# Power_Supply.net
KiCad netlist of a schematic drawn in Altium Designer
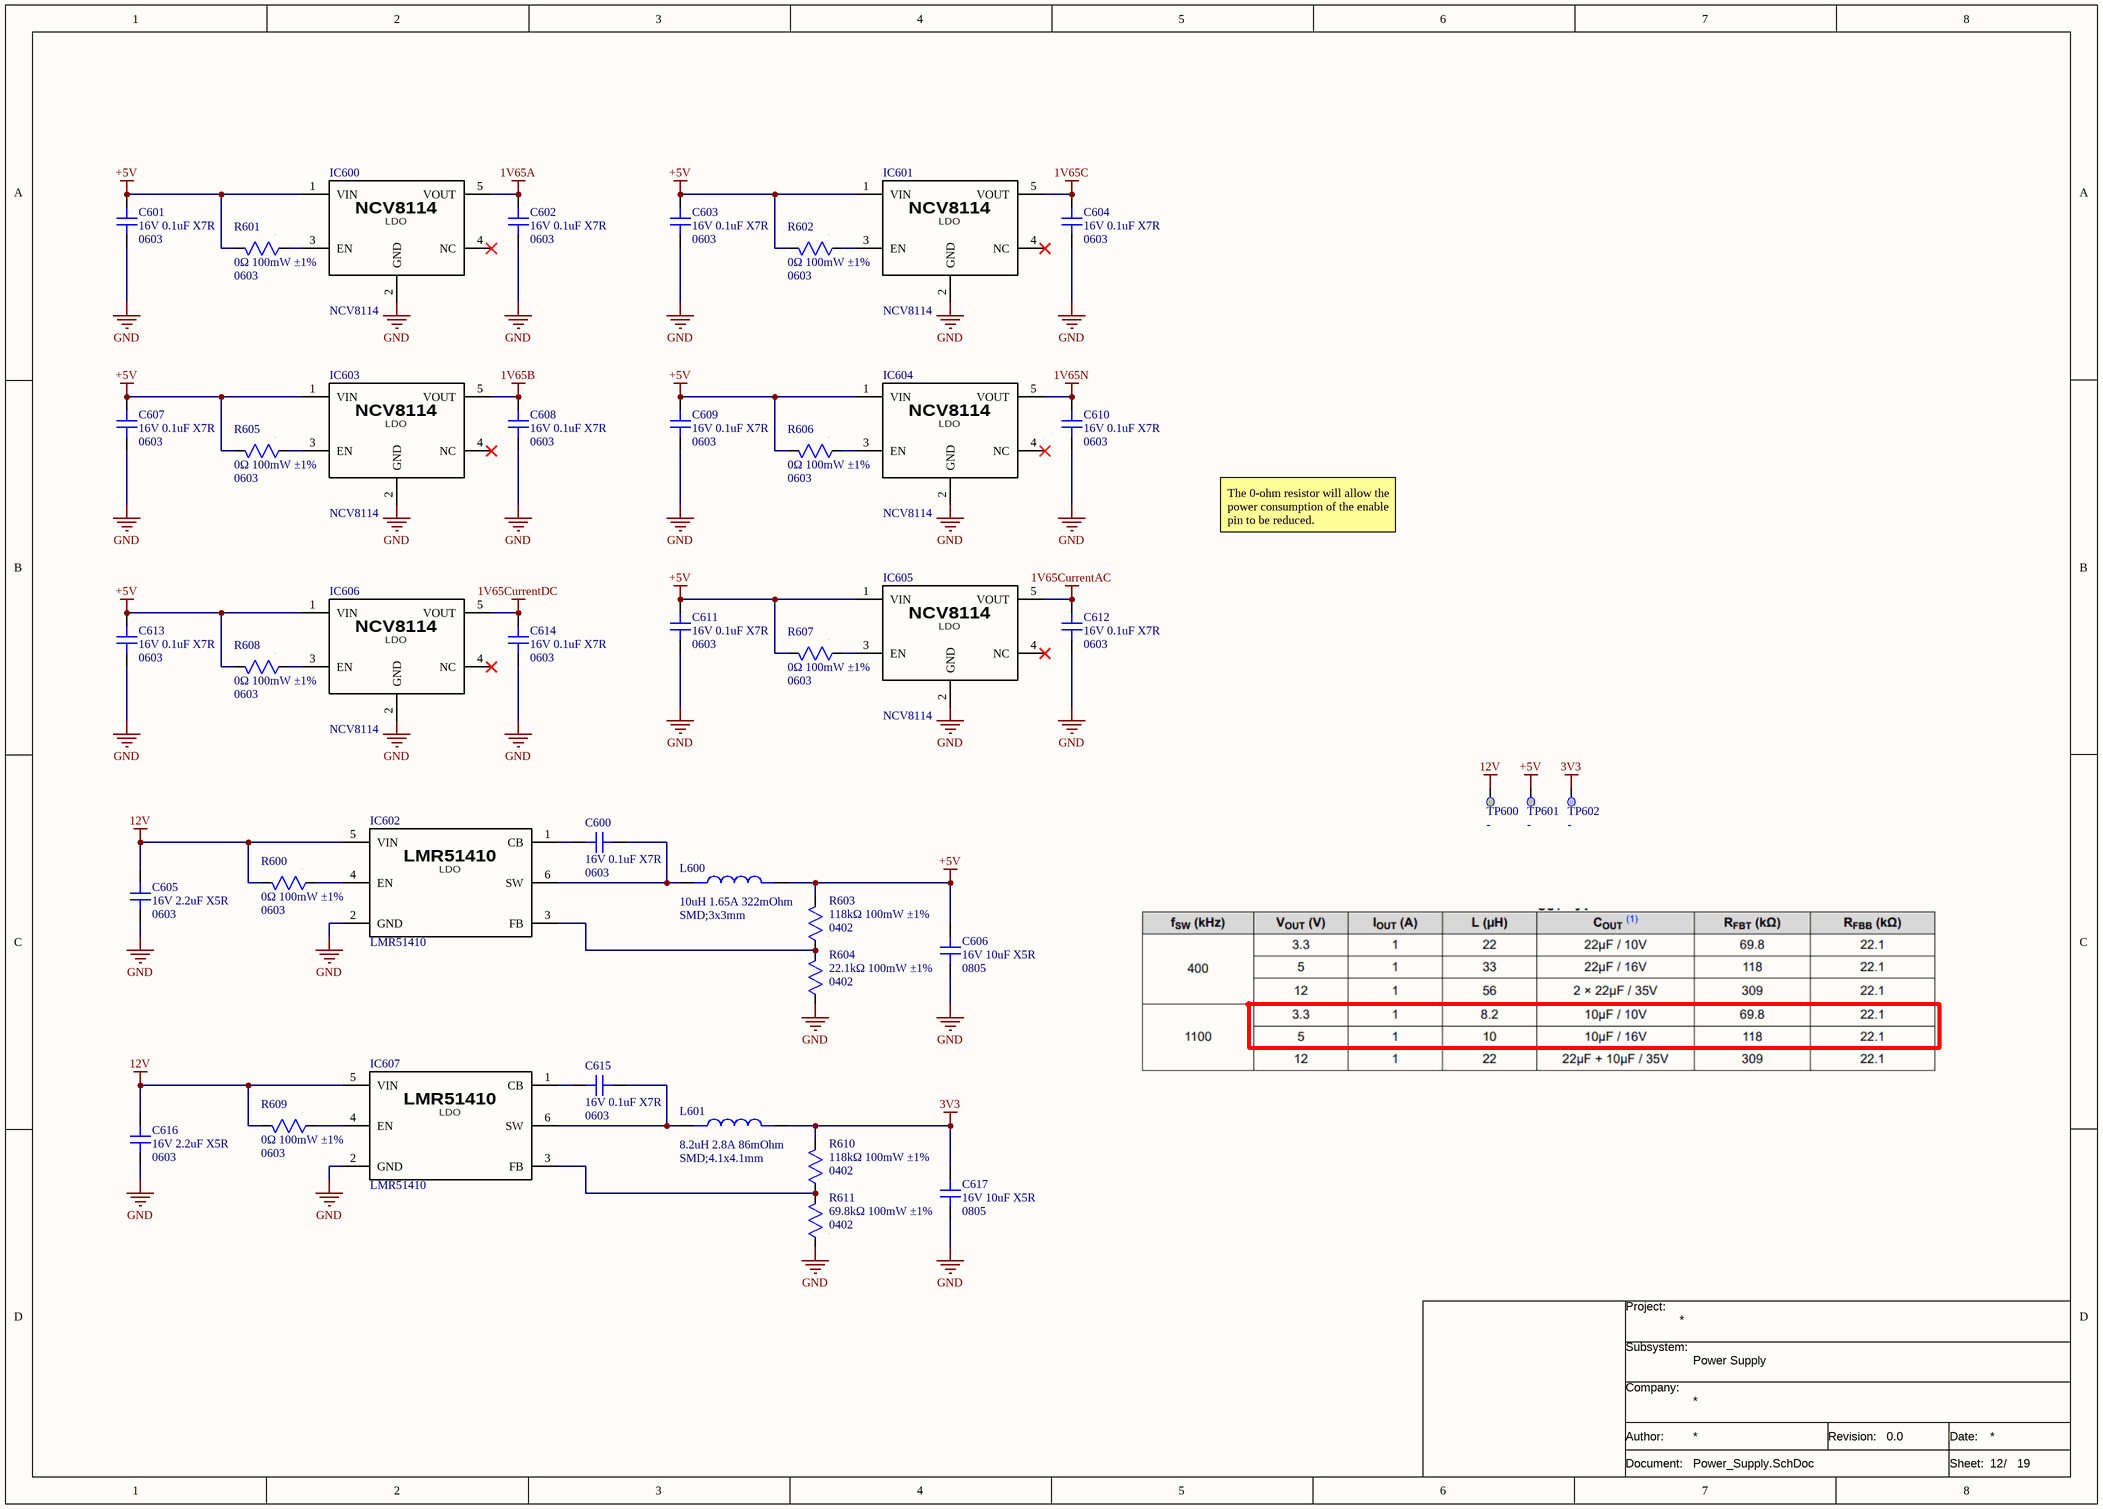
[diagram p0: Power_Supply.SchDoc]

(export (version "E")
  (design (tool "Eeschema 10.0.6"))
  (components
    (comp (ref "C600")
      (value "16V 0.1uF X7R")
      (footprint "CAP SMD 0603")
      (description "Condensadores de cerámica multicapa (MLCC- SMD/SMT) WCAP-CSGP 0.1uF 0603 10% 16V MLCC")
      (fields
        (field (name "PACKAGE") "0603")
        (field (name "MPN") "885012206046")
        (field (name "MANUFACTURER") "Wurth Elektronik")
      )
      (libsource (lib "eUSR_Database") (part "CAP non polarized"))
    )
    (comp (ref "C601")
      (value "16V 0.1uF X7R")
      (footprint "CAP SMD 0603")
      (description "Condensadores de cerámica multicapa (MLCC- SMD/SMT) WCAP-CSGP 0.1uF 0603 10% 16V MLCC")
      (fields
        (field (name "PACKAGE") "0603")
        (field (name "MPN") "885012206046")
        (field (name "MANUFACTURER") "Wurth Elektronik")
      )
      (libsource (lib "eUSR_Database") (part "CAP non polarized"))
    )
    (comp (ref "C602")
      (value "16V 0.1uF X7R")
      (footprint "CAP SMD 0603")
      (description "Condensadores de cerámica multicapa (MLCC- SMD/SMT) WCAP-CSGP 0.1uF 0603 10% 16V MLCC")
      (fields
        (field (name "PACKAGE") "0603")
        (field (name "MPN") "885012206046")
        (field (name "MANUFACTURER") "Wurth Elektronik")
      )
      (libsource (lib "eUSR_Database") (part "CAP non polarized"))
    )
    (comp (ref "C603")
      (value "16V 0.1uF X7R")
      (footprint "CAP SMD 0603")
      (description "Condensadores de cerámica multicapa (MLCC- SMD/SMT) WCAP-CSGP 0.1uF 0603 10% 16V MLCC")
      (fields
        (field (name "PACKAGE") "0603")
        (field (name "MPN") "885012206046")
        (field (name "MANUFACTURER") "Wurth Elektronik")
      )
      (libsource (lib "eUSR_Database") (part "CAP non polarized"))
    )
    (comp (ref "C604")
      (value "16V 0.1uF X7R")
      (footprint "CAP SMD 0603")
      (description "Condensadores de cerámica multicapa (MLCC- SMD/SMT) WCAP-CSGP 0.1uF 0603 10% 16V MLCC")
      (fields
        (field (name "PACKAGE") "0603")
        (field (name "MPN") "885012206046")
        (field (name "MANUFACTURER") "Wurth Elektronik")
      )
      (libsource (lib "eUSR_Database") (part "CAP non polarized"))
    )
    (comp (ref "C605")
      (value "16V 2.2uF X5R")
      (footprint "CAP SMD 0603")
      (description "Condensadores de cerámica multicapa (MLCC- SMD/SMT) WCAP-CSGP 2.2uF 16V 10%")
      (fields
        (field (name "PACKAGE") "0603")
        (field (name "MPN") "885012106029")
        (field (name "MANUFACTURER") "Wurth Elektronik")
      )
      (libsource (lib "eUSR_Database") (part "CAP non polarized"))
    )
    (comp (ref "C606")
      (value "16V 10uF X5R")
      (footprint "CAP SMD 0805")
      (description "Condensadores de cerámica multicapa (MLCC- SMD/SMT) WCAP-CSGP 10uF 0805 20% 16V MLCC")
      (fields
        (field (name "PACKAGE") "0805")
        (field (name "MPN") "885012107014")
        (field (name "MANUFACTURER") "Wurth Elektronik")
      )
      (libsource (lib "eUSR_Database") (part "CAP non polarized"))
    )
    (comp (ref "C607")
      (value "16V 0.1uF X7R")
      (footprint "CAP SMD 0603")
      (description "Condensadores de cerámica multicapa (MLCC- SMD/SMT) WCAP-CSGP 0.1uF 0603 10% 16V MLCC")
      (fields
        (field (name "PACKAGE") "0603")
        (field (name "MPN") "885012206046")
        (field (name "MANUFACTURER") "Wurth Elektronik")
      )
      (libsource (lib "eUSR_Database") (part "CAP non polarized"))
    )
    (comp (ref "C608")
      (value "16V 0.1uF X7R")
      (footprint "CAP SMD 0603")
      (description "Condensadores de cerámica multicapa (MLCC- SMD/SMT) WCAP-CSGP 0.1uF 0603 10% 16V MLCC")
      (fields
        (field (name "PACKAGE") "0603")
        (field (name "MPN") "885012206046")
        (field (name "MANUFACTURER") "Wurth Elektronik")
      )
      (libsource (lib "eUSR_Database") (part "CAP non polarized"))
    )
    (comp (ref "C609")
      (value "16V 0.1uF X7R")
      (footprint "CAP SMD 0603")
      (description "Condensadores de cerámica multicapa (MLCC- SMD/SMT) WCAP-CSGP 0.1uF 0603 10% 16V MLCC")
      (fields
        (field (name "PACKAGE") "0603")
        (field (name "MPN") "885012206046")
        (field (name "MANUFACTURER") "Wurth Elektronik")
      )
      (libsource (lib "eUSR_Database") (part "CAP non polarized"))
    )
    (comp (ref "C610")
      (value "16V 0.1uF X7R")
      (footprint "CAP SMD 0603")
      (description "Condensadores de cerámica multicapa (MLCC- SMD/SMT) WCAP-CSGP 0.1uF 0603 10% 16V MLCC")
      (fields
        (field (name "PACKAGE") "0603")
        (field (name "MPN") "885012206046")
        (field (name "MANUFACTURER") "Wurth Elektronik")
      )
      (libsource (lib "eUSR_Database") (part "CAP non polarized"))
    )
    (comp (ref "C611")
      (value "16V 0.1uF X7R")
      (footprint "CAP SMD 0603")
      (description "Condensadores de cerámica multicapa (MLCC- SMD/SMT) WCAP-CSGP 0.1uF 0603 10% 16V MLCC")
      (fields
        (field (name "PACKAGE") "0603")
        (field (name "MPN") "885012206046")
        (field (name "MANUFACTURER") "Wurth Elektronik")
      )
      (libsource (lib "eUSR_Database") (part "CAP non polarized"))
    )
    (comp (ref "C612")
      (value "16V 0.1uF X7R")
      (footprint "CAP SMD 0603")
      (description "Condensadores de cerámica multicapa (MLCC- SMD/SMT) WCAP-CSGP 0.1uF 0603 10% 16V MLCC")
      (fields
        (field (name "PACKAGE") "0603")
        (field (name "MPN") "885012206046")
        (field (name "MANUFACTURER") "Wurth Elektronik")
      )
      (libsource (lib "eUSR_Database") (part "CAP non polarized"))
    )
    (comp (ref "C613")
      (value "16V 0.1uF X7R")
      (footprint "CAP SMD 0603")
      (description "Condensadores de cerámica multicapa (MLCC- SMD/SMT) WCAP-CSGP 0.1uF 0603 10% 16V MLCC")
      (fields
        (field (name "PACKAGE") "0603")
        (field (name "MPN") "885012206046")
        (field (name "MANUFACTURER") "Wurth Elektronik")
      )
      (libsource (lib "eUSR_Database") (part "CAP non polarized"))
    )
    (comp (ref "C614")
      (value "16V 0.1uF X7R")
      (footprint "CAP SMD 0603")
      (description "Condensadores de cerámica multicapa (MLCC- SMD/SMT) WCAP-CSGP 0.1uF 0603 10% 16V MLCC")
      (fields
        (field (name "PACKAGE") "0603")
        (field (name "MPN") "885012206046")
        (field (name "MANUFACTURER") "Wurth Elektronik")
      )
      (libsource (lib "eUSR_Database") (part "CAP non polarized"))
    )
    (comp (ref "C615")
      (value "16V 0.1uF X7R")
      (footprint "CAP SMD 0603")
      (description "Condensadores de cerámica multicapa (MLCC- SMD/SMT) WCAP-CSGP 0.1uF 0603 10% 16V MLCC")
      (fields
        (field (name "PACKAGE") "0603")
        (field (name "MPN") "885012206046")
        (field (name "MANUFACTURER") "Wurth Elektronik")
      )
      (libsource (lib "eUSR_Database") (part "CAP non polarized"))
    )
    (comp (ref "C616")
      (value "16V 2.2uF X5R")
      (footprint "CAP SMD 0603")
      (description "Condensadores de cerámica multicapa (MLCC- SMD/SMT) WCAP-CSGP 2.2uF 16V 10%")
      (fields
        (field (name "PACKAGE") "0603")
        (field (name "MPN") "885012106029")
        (field (name "MANUFACTURER") "Wurth Elektronik")
      )
      (libsource (lib "eUSR_Database") (part "CAP non polarized"))
    )
    (comp (ref "C617")
      (value "16V 10uF X5R")
      (footprint "CAP SMD 0805")
      (description "Condensadores de cerámica multicapa (MLCC- SMD/SMT) WCAP-CSGP 10uF 0805 20% 16V MLCC")
      (fields
        (field (name "PACKAGE") "0805")
        (field (name "MPN") "885012107014")
        (field (name "MANUFACTURER") "Wurth Elektronik")
      )
      (libsource (lib "eUSR_Database") (part "CAP non polarized"))
    )
    (comp (ref "IC600")
      (value "NCV8114")
      (footprint "SOT-23-5")
      (description "Reguladores de voltaje LDO 300 MA CMOS LDO, AD OPTIO")
      (fields (field (name "MPN") "NCV8114ASN165T1G") (field (name "MANUFACTURER") "onsemi"))
      (libsource (lib "eUSR_Database") (part "NCV8114"))
    )
    (comp (ref "IC601")
      (value "NCV8114")
      (footprint "SOT-23-5")
      (description "Reguladores de voltaje LDO 300 MA CMOS LDO, AD OPTIO")
      (fields (field (name "MPN") "NCV8114ASN165T1G") (field (name "MANUFACTURER") "onsemi"))
      (libsource (lib "eUSR_Database") (part "NCV8114"))
    )
    (comp (ref "IC602")
      (value "LMR51410")
      (footprint "SOT-23-6")
      (description "Reguladores de tensión de conmutación SIMPLE SWITCHER 4V t o 42V 1A synchronou")
      (fields (field (name "MPN") "LMR51410YFDBVR") (field (name "MANUFACTURER") "Texas Instruments"))
      (libsource (lib "eUSR_Database") (part "LMR51410"))
    )
    (comp (ref "IC603")
      (value "NCV8114")
      (footprint "SOT-23-5")
      (description "Reguladores de voltaje LDO 300 MA CMOS LDO, AD OPTIO")
      (fields (field (name "MPN") "NCV8114ASN165T1G") (field (name "MANUFACTURER") "onsemi"))
      (libsource (lib "eUSR_Database") (part "NCV8114"))
    )
    (comp (ref "IC604")
      (value "NCV8114")
      (footprint "SOT-23-5")
      (description "Reguladores de voltaje LDO 300 MA CMOS LDO, AD OPTIO")
      (fields (field (name "MPN") "NCV8114ASN165T1G") (field (name "MANUFACTURER") "onsemi"))
      (libsource (lib "eUSR_Database") (part "NCV8114"))
    )
    (comp (ref "IC605")
      (value "NCV8114")
      (footprint "SOT-23-5")
      (description "Reguladores de voltaje LDO 300 MA CMOS LDO, AD OPTIO")
      (fields (field (name "MPN") "NCV8114ASN165T1G") (field (name "MANUFACTURER") "onsemi"))
      (libsource (lib "eUSR_Database") (part "NCV8114"))
    )
    (comp (ref "IC606")
      (value "NCV8114")
      (footprint "SOT-23-5")
      (description "Reguladores de voltaje LDO 300 MA CMOS LDO, AD OPTIO")
      (fields (field (name "MPN") "NCV8114ASN165T1G") (field (name "MANUFACTURER") "onsemi"))
      (libsource (lib "eUSR_Database") (part "NCV8114"))
    )
    (comp (ref "IC607")
      (value "LMR51410")
      (footprint "SOT-23-6")
      (description "Reguladores de tensión de conmutación SIMPLE SWITCHER 4V t o 42V 1A synchronou")
      (fields (field (name "MPN") "LMR51410YFDBVR") (field (name "MANUFACTURER") "Texas Instruments"))
      (libsource (lib "eUSR_Database") (part "LMR51410"))
    )
    (comp (ref "L600")
      (value "10uH 1.65A 322mOhm")
      (footprint "IND SMD 3x3")
      (description "Inductores de potencia (SMD) WE-MAPI 10uH 1.2A DCR=322mOhms AEC-Q200")
      (fields
        (field (name "PACKAGE") "SMD;3x3mm")
        (field (name "MPN") "74438336100")
        (field (name "MANUFACTURER") "Wurth Elektronik")
      )
      (libsource (lib "eUSR_Database") (part "IND"))
    )
    (comp (ref "L601")
      (value "8.2uH 2.8A 86mOhm")
      (footprint "IND SMD 4.1x4.1")
      (description "Inductores de potencia (SMD) WE-MAPI 8.2uH 2.8A DCR=86mOhms AEC-Q200")
      (fields
        (field (name "PACKAGE") "SMD;4.1x4.1mm")
        (field (name "MPN") "74438357082")
        (field (name "MANUFACTURER") "Wurth Elektronik")
      )
      (libsource (lib "eUSR_Database") (part "IND"))
    )
    (comp (ref "R600")
      (value "0Ω 100mW ±1%")
      (footprint "RES SMD 0603")
      (description "Resistores de película gruesa - SMD WRIS-RSKS <0.05 Ohms 0.1 W Jumper 0603 AEC-Q200")
      (fields
        (field (name "PACKAGE") "0603")
        (field (name "MPN") "5,60112116e+11")
        (field (name "MANUFACTURER") "Wurth Elektronik")
      )
      (libsource (lib "eUSR_Database") (part "RES"))
    )
    (comp (ref "R601")
      (value "0Ω 100mW ±1%")
      (footprint "RES SMD 0603")
      (description "Resistores de película gruesa - SMD WRIS-RSKS <0.05 Ohms 0.1 W Jumper 0603 AEC-Q200")
      (fields
        (field (name "PACKAGE") "0603")
        (field (name "MPN") "5,60112116e+11")
        (field (name "MANUFACTURER") "Wurth Elektronik")
      )
      (libsource (lib "eUSR_Database") (part "RES"))
    )
    (comp (ref "R602")
      (value "0Ω 100mW ±1%")
      (footprint "RES SMD 0603")
      (description "Resistores de película gruesa - SMD WRIS-RSKS <0.05 Ohms 0.1 W Jumper 0603 AEC-Q200")
      (fields
        (field (name "PACKAGE") "0603")
        (field (name "MPN") "5,60112116e+11")
        (field (name "MANUFACTURER") "Wurth Elektronik")
      )
      (libsource (lib "eUSR_Database") (part "RES"))
    )
    (comp (ref "R603")
      (value "118kΩ 100mW ±1%")
      (footprint "RES SMD 0402")
      (description "Resistores de película gruesa - SMD WRIS-RSKS 118 kOhms 1 % 0.1 W 0402 AEC-Q200")
      (fields
        (field (name "PACKAGE") "0402")
        (field (name "MPN") "560112110142")
        (field (name "MANUFACTURER") "Wurth Elektronik")
      )
      (libsource (lib "eUSR_Database") (part "RES"))
    )
    (comp (ref "R604")
      (value "22.1kΩ 100mW ±1%")
      (footprint "RES SMD 0402")
      (description "Resistores de película gruesa - SMD WRIS-RSKS 22.1 kOhms 1 % 0.1 W 0402 AEC-Q200")
      (fields
        (field (name "PACKAGE") "0402")
        (field (name "MPN") "560112110099")
        (field (name "MANUFACTURER") "Wurth Elektronik")
      )
      (libsource (lib "eUSR_Database") (part "RES"))
    )
    (comp (ref "R605")
      (value "0Ω 100mW ±1%")
      (footprint "RES SMD 0603")
      (description "Resistores de película gruesa - SMD WRIS-RSKS <0.05 Ohms 0.1 W Jumper 0603 AEC-Q200")
      (fields
        (field (name "PACKAGE") "0603")
        (field (name "MPN") "5,60112116e+11")
        (field (name "MANUFACTURER") "Wurth Elektronik")
      )
      (libsource (lib "eUSR_Database") (part "RES"))
    )
    (comp (ref "R606")
      (value "0Ω 100mW ±1%")
      (footprint "RES SMD 0603")
      (description "Resistores de película gruesa - SMD WRIS-RSKS <0.05 Ohms 0.1 W Jumper 0603 AEC-Q200")
      (fields
        (field (name "PACKAGE") "0603")
        (field (name "MPN") "5,60112116e+11")
        (field (name "MANUFACTURER") "Wurth Elektronik")
      )
      (libsource (lib "eUSR_Database") (part "RES"))
    )
    (comp (ref "R607")
      (value "0Ω 100mW ±1%")
      (footprint "RES SMD 0603")
      (description "Resistores de película gruesa - SMD WRIS-RSKS <0.05 Ohms 0.1 W Jumper 0603 AEC-Q200")
      (fields
        (field (name "PACKAGE") "0603")
        (field (name "MPN") "5,60112116e+11")
        (field (name "MANUFACTURER") "Wurth Elektronik")
      )
      (libsource (lib "eUSR_Database") (part "RES"))
    )
    (comp (ref "R608")
      (value "0Ω 100mW ±1%")
      (footprint "RES SMD 0603")
      (description "Resistores de película gruesa - SMD WRIS-RSKS <0.05 Ohms 0.1 W Jumper 0603 AEC-Q200")
      (fields
        (field (name "PACKAGE") "0603")
        (field (name "MPN") "5,60112116e+11")
        (field (name "MANUFACTURER") "Wurth Elektronik")
      )
      (libsource (lib "eUSR_Database") (part "RES"))
    )
    (comp (ref "R609")
      (value "0Ω 100mW ±1%")
      (footprint "RES SMD 0603")
      (description "Resistores de película gruesa - SMD WRIS-RSKS <0.05 Ohms 0.1 W Jumper 0603 AEC-Q200")
      (fields
        (field (name "PACKAGE") "0603")
        (field (name "MPN") "5,60112116e+11")
        (field (name "MANUFACTURER") "Wurth Elektronik")
      )
      (libsource (lib "eUSR_Database") (part "RES"))
    )
    (comp (ref "R610")
      (value "118kΩ 100mW ±1%")
      (footprint "RES SMD 0402")
      (description "Resistores de película gruesa - SMD WRIS-RSKS 118 kOhms 1 % 0.1 W 0402 AEC-Q200")
      (fields
        (field (name "PACKAGE") "0402")
        (field (name "MPN") "560112110142")
        (field (name "MANUFACTURER") "Wurth Elektronik")
      )
      (libsource (lib "eUSR_Database") (part "RES"))
    )
    (comp (ref "R611")
      (value "69.8kΩ 100mW ±1%")
      (footprint "RES SMD 0402")
      (description "Resistores de película gruesa - SMD 1/10 Watt 69.8Kohms 1%")
      (fields
        (field (name "PACKAGE") "0402")
        (field (name "MPN") "CRCW040269K8FKED")
        (field (name "MANUFACTURER") "Vishay")
      )
      (libsource (lib "eUSR_Database") (part "RES"))
    )
    (comp (ref "TP600")
      (value "-")
      (footprint "TP_SMD_1MM")
      (description "Test Point")
      (libsource (lib "eUSR_Database") (part "TP1mm"))
    )
    (comp (ref "TP601")
      (value "-")
      (footprint "TP_SMD_1MM")
      (description "Test Point")
      (libsource (lib "eUSR_Database") (part "TP1mm"))
    )
    (comp (ref "TP602")
      (value "-")
      (footprint "TP_SMD_1MM")
      (description "Test Point")
      (libsource (lib "eUSR_Database") (part "TP1mm"))
    )
  )
  (nets
    (net (code "1") (name "+5V") (class "Default")
      (node (ref "C601") (pin "2") (pinfunction "2_2") (pintype "passive"))
      (node (ref "C603") (pin "2") (pinfunction "2_2") (pintype "passive"))
      (node (ref "C606") (pin "1") (pinfunction "1_1") (pintype "passive"))
      (node (ref "C607") (pin "2") (pinfunction "2_2") (pintype "passive"))
      (node (ref "C609") (pin "2") (pinfunction "2_2") (pintype "passive"))
      (node (ref "C611") (pin "2") (pinfunction "2_2") (pintype "passive"))
      (node (ref "C613") (pin "2") (pinfunction "2_2") (pintype "passive"))
      (node (ref "IC600") (pin "1") (pinfunction "VIN_1") (pintype "passive"))
      (node (ref "IC601") (pin "1") (pinfunction "VIN_1") (pintype "passive"))
      (node (ref "IC603") (pin "1") (pinfunction "VIN_1") (pintype "passive"))
      (node (ref "IC604") (pin "1") (pinfunction "VIN_1") (pintype "passive"))
      (node (ref "IC605") (pin "1") (pinfunction "VIN_1") (pintype "passive"))
      (node (ref "IC606") (pin "1") (pinfunction "VIN_1") (pintype "passive"))
      (node (ref "L600") (pin "2") (pinfunction "2_2") (pintype "passive"))
      (node (ref "R601") (pin "2") (pinfunction "2_2") (pintype "passive"))
      (node (ref "R602") (pin "2") (pinfunction "2_2") (pintype "passive"))
      (node (ref "R603") (pin "2") (pinfunction "2_2") (pintype "passive"))
      (node (ref "R605") (pin "2") (pinfunction "2_2") (pintype "passive"))
      (node (ref "R606") (pin "2") (pinfunction "2_2") (pintype "passive"))
      (node (ref "R607") (pin "2") (pinfunction "2_2") (pintype "passive"))
      (node (ref "R608") (pin "2") (pinfunction "2_2") (pintype "passive"))
      (node (ref "TP601") (pin "1") (pinfunction "1_1") (pintype "passive"))
    )
    (net (code "2") (name "1V65A") (class "Default")
      (node (ref "C602") (pin "2") (pinfunction "2_2") (pintype "passive"))
      (node (ref "IC600") (pin "5") (pinfunction "VOUT_5") (pintype "passive"))
    )
    (net (code "3") (name "1V65B") (class "Default")
      (node (ref "C608") (pin "2") (pinfunction "2_2") (pintype "passive"))
      (node (ref "IC603") (pin "5") (pinfunction "VOUT_5") (pintype "passive"))
    )
    (net (code "4") (name "1V65C") (class "Default")
      (node (ref "C604") (pin "2") (pinfunction "2_2") (pintype "passive"))
      (node (ref "IC601") (pin "5") (pinfunction "VOUT_5") (pintype "passive"))
    )
    (net (code "5") (name "1V65CurrentAC") (class "Default")
      (node (ref "C612") (pin "2") (pinfunction "2_2") (pintype "passive"))
      (node (ref "IC605") (pin "5") (pinfunction "VOUT_5") (pintype "passive"))
    )
    (net (code "6") (name "1V65CurrentDC") (class "Default")
      (node (ref "C614") (pin "2") (pinfunction "2_2") (pintype "passive"))
      (node (ref "IC606") (pin "5") (pinfunction "VOUT_5") (pintype "passive"))
    )
    (net (code "7") (name "1V65N") (class "Default")
      (node (ref "C610") (pin "2") (pinfunction "2_2") (pintype "passive"))
      (node (ref "IC604") (pin "5") (pinfunction "VOUT_5") (pintype "passive"))
    )
    (net (code "8") (name "3V3") (class "Default")
      (node (ref "C617") (pin "1") (pinfunction "1_1") (pintype "passive"))
      (node (ref "L601") (pin "2") (pinfunction "2_2") (pintype "passive"))
      (node (ref "R610") (pin "2") (pinfunction "2_2") (pintype "passive"))
      (node (ref "TP602") (pin "1") (pinfunction "1_1") (pintype "passive"))
    )
    (net (code "9") (name "12V") (class "Default")
      (node (ref "C605") (pin "1") (pinfunction "1_1") (pintype "passive"))
      (node (ref "C616") (pin "1") (pinfunction "1_1") (pintype "passive"))
      (node (ref "IC602") (pin "5") (pinfunction "VIN_5") (pintype "passive"))
      (node (ref "IC607") (pin "5") (pinfunction "VIN_5") (pintype "passive"))
      (node (ref "R600") (pin "2") (pinfunction "2_2") (pintype "passive"))
      (node (ref "R609") (pin "2") (pinfunction "2_2") (pintype "passive"))
      (node (ref "TP600") (pin "1") (pinfunction "1_1") (pintype "passive"))
    )
    (net (code "10") (name "GND") (class "Default")
      (node (ref "C601") (pin "1") (pinfunction "1_1") (pintype "passive"))
      (node (ref "C602") (pin "1") (pinfunction "1_1") (pintype "passive"))
      (node (ref "C603") (pin "1") (pinfunction "1_1") (pintype "passive"))
      (node (ref "C604") (pin "1") (pinfunction "1_1") (pintype "passive"))
      (node (ref "C605") (pin "2") (pinfunction "2_2") (pintype "passive"))
      (node (ref "C606") (pin "2") (pinfunction "2_2") (pintype "passive"))
      (node (ref "C607") (pin "1") (pinfunction "1_1") (pintype "passive"))
      (node (ref "C608") (pin "1") (pinfunction "1_1") (pintype "passive"))
      (node (ref "C609") (pin "1") (pinfunction "1_1") (pintype "passive"))
      (node (ref "C610") (pin "1") (pinfunction "1_1") (pintype "passive"))
      (node (ref "C611") (pin "1") (pinfunction "1_1") (pintype "passive"))
      (node (ref "C612") (pin "1") (pinfunction "1_1") (pintype "passive"))
      (node (ref "C613") (pin "1") (pinfunction "1_1") (pintype "passive"))
      (node (ref "C614") (pin "1") (pinfunction "1_1") (pintype "passive"))
      (node (ref "C616") (pin "2") (pinfunction "2_2") (pintype "passive"))
      (node (ref "C617") (pin "2") (pinfunction "2_2") (pintype "passive"))
      (node (ref "IC600") (pin "2") (pinfunction "GND_2") (pintype "passive"))
      (node (ref "IC601") (pin "2") (pinfunction "GND_2") (pintype "passive"))
      (node (ref "IC602") (pin "2") (pinfunction "GND_2") (pintype "passive"))
      (node (ref "IC603") (pin "2") (pinfunction "GND_2") (pintype "passive"))
      (node (ref "IC604") (pin "2") (pinfunction "GND_2") (pintype "passive"))
      (node (ref "IC605") (pin "2") (pinfunction "GND_2") (pintype "passive"))
      (node (ref "IC606") (pin "2") (pinfunction "GND_2") (pintype "passive"))
      (node (ref "IC607") (pin "2") (pinfunction "GND_2") (pintype "passive"))
      (node (ref "R604") (pin "1") (pinfunction "1_1") (pintype "passive"))
      (node (ref "R611") (pin "1") (pinfunction "1_1") (pintype "passive"))
    )
    (net (code "11") (name "Net-(IC600-EN)") (class "Default")
      (node (ref "IC600") (pin "3") (pinfunction "EN_3") (pintype "passive"))
      (node (ref "R601") (pin "1") (pinfunction "1_1") (pintype "passive"))
    )
    (net (code "12") (name "Net-(IC601-EN)") (class "Default")
      (node (ref "IC601") (pin "3") (pinfunction "EN_3") (pintype "passive"))
      (node (ref "R602") (pin "1") (pinfunction "1_1") (pintype "passive"))
    )
    (net (code "13") (name "Net-(IC602-CB)") (class "Default")
      (node (ref "C600") (pin "1") (pinfunction "1_1") (pintype "passive"))
      (node (ref "IC602") (pin "1") (pinfunction "CB_1") (pintype "passive"))
    )
    (net (code "14") (name "Net-(IC602-EN)") (class "Default")
      (node (ref "IC602") (pin "4") (pinfunction "EN_4") (pintype "passive"))
      (node (ref "R600") (pin "1") (pinfunction "1_1") (pintype "passive"))
    )
    (net (code "15") (name "Net-(IC602-FB)") (class "Default")
      (node (ref "IC602") (pin "3") (pinfunction "FB_3") (pintype "passive"))
      (node (ref "R603") (pin "1") (pinfunction "1_1") (pintype "passive"))
      (node (ref "R604") (pin "2") (pinfunction "2_2") (pintype "passive"))
    )
    (net (code "16") (name "Net-(IC602-SW)") (class "Default")
      (node (ref "C600") (pin "2") (pinfunction "2_2") (pintype "passive"))
      (node (ref "IC602") (pin "6") (pinfunction "SW_6") (pintype "passive"))
      (node (ref "L600") (pin "1") (pinfunction "1_1") (pintype "passive"))
    )
    (net (code "17") (name "Net-(IC603-EN)") (class "Default")
      (node (ref "IC603") (pin "3") (pinfunction "EN_3") (pintype "passive"))
      (node (ref "R605") (pin "1") (pinfunction "1_1") (pintype "passive"))
    )
    (net (code "18") (name "Net-(IC604-EN)") (class "Default")
      (node (ref "IC604") (pin "3") (pinfunction "EN_3") (pintype "passive"))
      (node (ref "R606") (pin "1") (pinfunction "1_1") (pintype "passive"))
    )
    (net (code "19") (name "Net-(IC605-EN)") (class "Default")
      (node (ref "IC605") (pin "3") (pinfunction "EN_3") (pintype "passive"))
      (node (ref "R607") (pin "1") (pinfunction "1_1") (pintype "passive"))
    )
    (net (code "20") (name "Net-(IC606-EN)") (class "Default")
      (node (ref "IC606") (pin "3") (pinfunction "EN_3") (pintype "passive"))
      (node (ref "R608") (pin "1") (pinfunction "1_1") (pintype "passive"))
    )
    (net (code "21") (name "Net-(IC607-CB)") (class "Default")
      (node (ref "C615") (pin "1") (pinfunction "1_1") (pintype "passive"))
      (node (ref "IC607") (pin "1") (pinfunction "CB_1") (pintype "passive"))
    )
    (net (code "22") (name "Net-(IC607-EN)") (class "Default")
      (node (ref "IC607") (pin "4") (pinfunction "EN_4") (pintype "passive"))
      (node (ref "R609") (pin "1") (pinfunction "1_1") (pintype "passive"))
    )
    (net (code "23") (name "Net-(IC607-FB)") (class "Default")
      (node (ref "IC607") (pin "3") (pinfunction "FB_3") (pintype "passive"))
      (node (ref "R610") (pin "1") (pinfunction "1_1") (pintype "passive"))
      (node (ref "R611") (pin "2") (pinfunction "2_2") (pintype "passive"))
    )
    (net (code "24") (name "Net-(IC607-SW)") (class "Default")
      (node (ref "C615") (pin "2") (pinfunction "2_2") (pintype "passive"))
      (node (ref "IC607") (pin "6") (pinfunction "SW_6") (pintype "passive"))
      (node (ref "L601") (pin "1") (pinfunction "1_1") (pintype "passive"))
    )
    (net (code "25") (name "unconnected-(IC600-NC-Pad4)") (class "Default")
      (node (ref "IC600") (pin "4") (pinfunction "NC_4") (pintype "passive+no_connect"))
    )
    (net (code "26") (name "unconnected-(IC601-NC-Pad4)") (class "Default")
      (node (ref "IC601") (pin "4") (pinfunction "NC_4") (pintype "passive+no_connect"))
    )
    (net (code "27") (name "unconnected-(IC603-NC-Pad4)") (class "Default")
      (node (ref "IC603") (pin "4") (pinfunction "NC_4") (pintype "passive+no_connect"))
    )
    (net (code "28") (name "unconnected-(IC604-NC-Pad4)") (class "Default")
      (node (ref "IC604") (pin "4") (pinfunction "NC_4") (pintype "passive+no_connect"))
    )
    (net (code "29") (name "unconnected-(IC605-NC-Pad4)") (class "Default")
      (node (ref "IC605") (pin "4") (pinfunction "NC_4") (pintype "passive+no_connect"))
    )
    (net (code "30") (name "unconnected-(IC606-NC-Pad4)") (class "Default")
      (node (ref "IC606") (pin "4") (pinfunction "NC_4") (pintype "passive+no_connect"))
    )
  )
)
